# CNY70.net
KiCad netlist of a schematic drawn in EAGLE
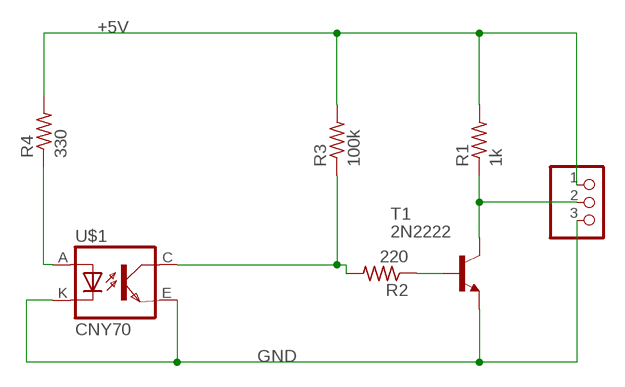
[diagram p0: schematic, sheet 1]

(export (version "E")
  (design (tool "Eeschema 10.0.6"))
  (components
    (comp (ref "JP1")
      (value "PINHD-1X3")
      (footprint "eagle-import:1X03")
      (libsource (lib "eagle-import") (part "PINHD-1X3"))
    )
    (comp (ref "R1")
      (value "1k")
      (footprint "eagle-import:0207_10")
      (libsource (lib "eagle-import") (part "R-US_0207/10"))
    )
    (comp (ref "R2")
      (value "220")
      (footprint "eagle-import:0207_10")
      (libsource (lib "eagle-import") (part "R-US_0207/10"))
    )
    (comp (ref "R3")
      (value "100k")
      (footprint "eagle-import:0207_10")
      (libsource (lib "eagle-import") (part "R-US_0207/10"))
    )
    (comp (ref "R4")
      (value "330")
      (footprint "eagle-import:0207_10")
      (libsource (lib "eagle-import") (part "R-US_0207/10"))
    )
    (comp (ref "T1")
      (value "2N2222")
      (footprint "eagle-import:TO92-EBC-OVAL")
      (libsource (lib "eagle-import") (part "2N2222"))
    )
    (comp (ref "U$1")
      (value "CNY70")
      (footprint "eagle-import:4")
      (libsource (lib "eagle-import") (part "CNY70"))
    )
  )
  (nets
    (net (code "1") (name "/+5V") (class "Default")
      (node (ref "JP1") (pin "1") (pinfunction "1_1") (pintype "passive"))
      (node (ref "R1") (pin "2") (pinfunction "2_2") (pintype "passive"))
      (node (ref "R3") (pin "2") (pinfunction "2_2") (pintype "passive"))
      (node (ref "R4") (pin "2") (pinfunction "2_2") (pintype "passive"))
    )
    (net (code "2") (name "/GND") (class "Default")
      (node (ref "JP1") (pin "3") (pinfunction "3_3") (pintype "passive"))
      (node (ref "T1") (pin "E") (pinfunction "E_E") (pintype "passive"))
      (node (ref "U$1") (pin "E") (pinfunction "EMI_E") (pintype "passive"))
      (node (ref "U$1") (pin "K") (pinfunction "C_K") (pintype "passive"))
    )
    (net (code "3") (name "Net-(JP1-Pad2)") (class "Default")
      (node (ref "JP1") (pin "2") (pinfunction "2_2") (pintype "passive"))
      (node (ref "R1") (pin "1") (pinfunction "1_1") (pintype "passive"))
      (node (ref "T1") (pin "C") (pinfunction "C_C") (pintype "passive"))
    )
    (net (code "4") (name "Net-(R2-Pad1)") (class "Default")
      (node (ref "R2") (pin "1") (pinfunction "1_1") (pintype "passive"))
      (node (ref "T1") (pin "B") (pinfunction "B_B") (pintype "passive"))
    )
    (net (code "5") (name "Net-(R4-Pad1)") (class "Default")
      (node (ref "R4") (pin "1") (pinfunction "1_1") (pintype "passive"))
      (node (ref "U$1") (pin "A") (pinfunction "A_A") (pintype "passive"))
    )
    (net (code "6") (name "Net-(U$1-COL)") (class "Default")
      (node (ref "R2") (pin "2") (pinfunction "2_2") (pintype "passive"))
      (node (ref "R3") (pin "1") (pinfunction "1_1") (pintype "passive"))
      (node (ref "U$1") (pin "C") (pinfunction "COL_C") (pintype "passive"))
    )
  )
)
